# GalvoPrint.net
KiCad netlist of a schematic drawn in Altium Designer
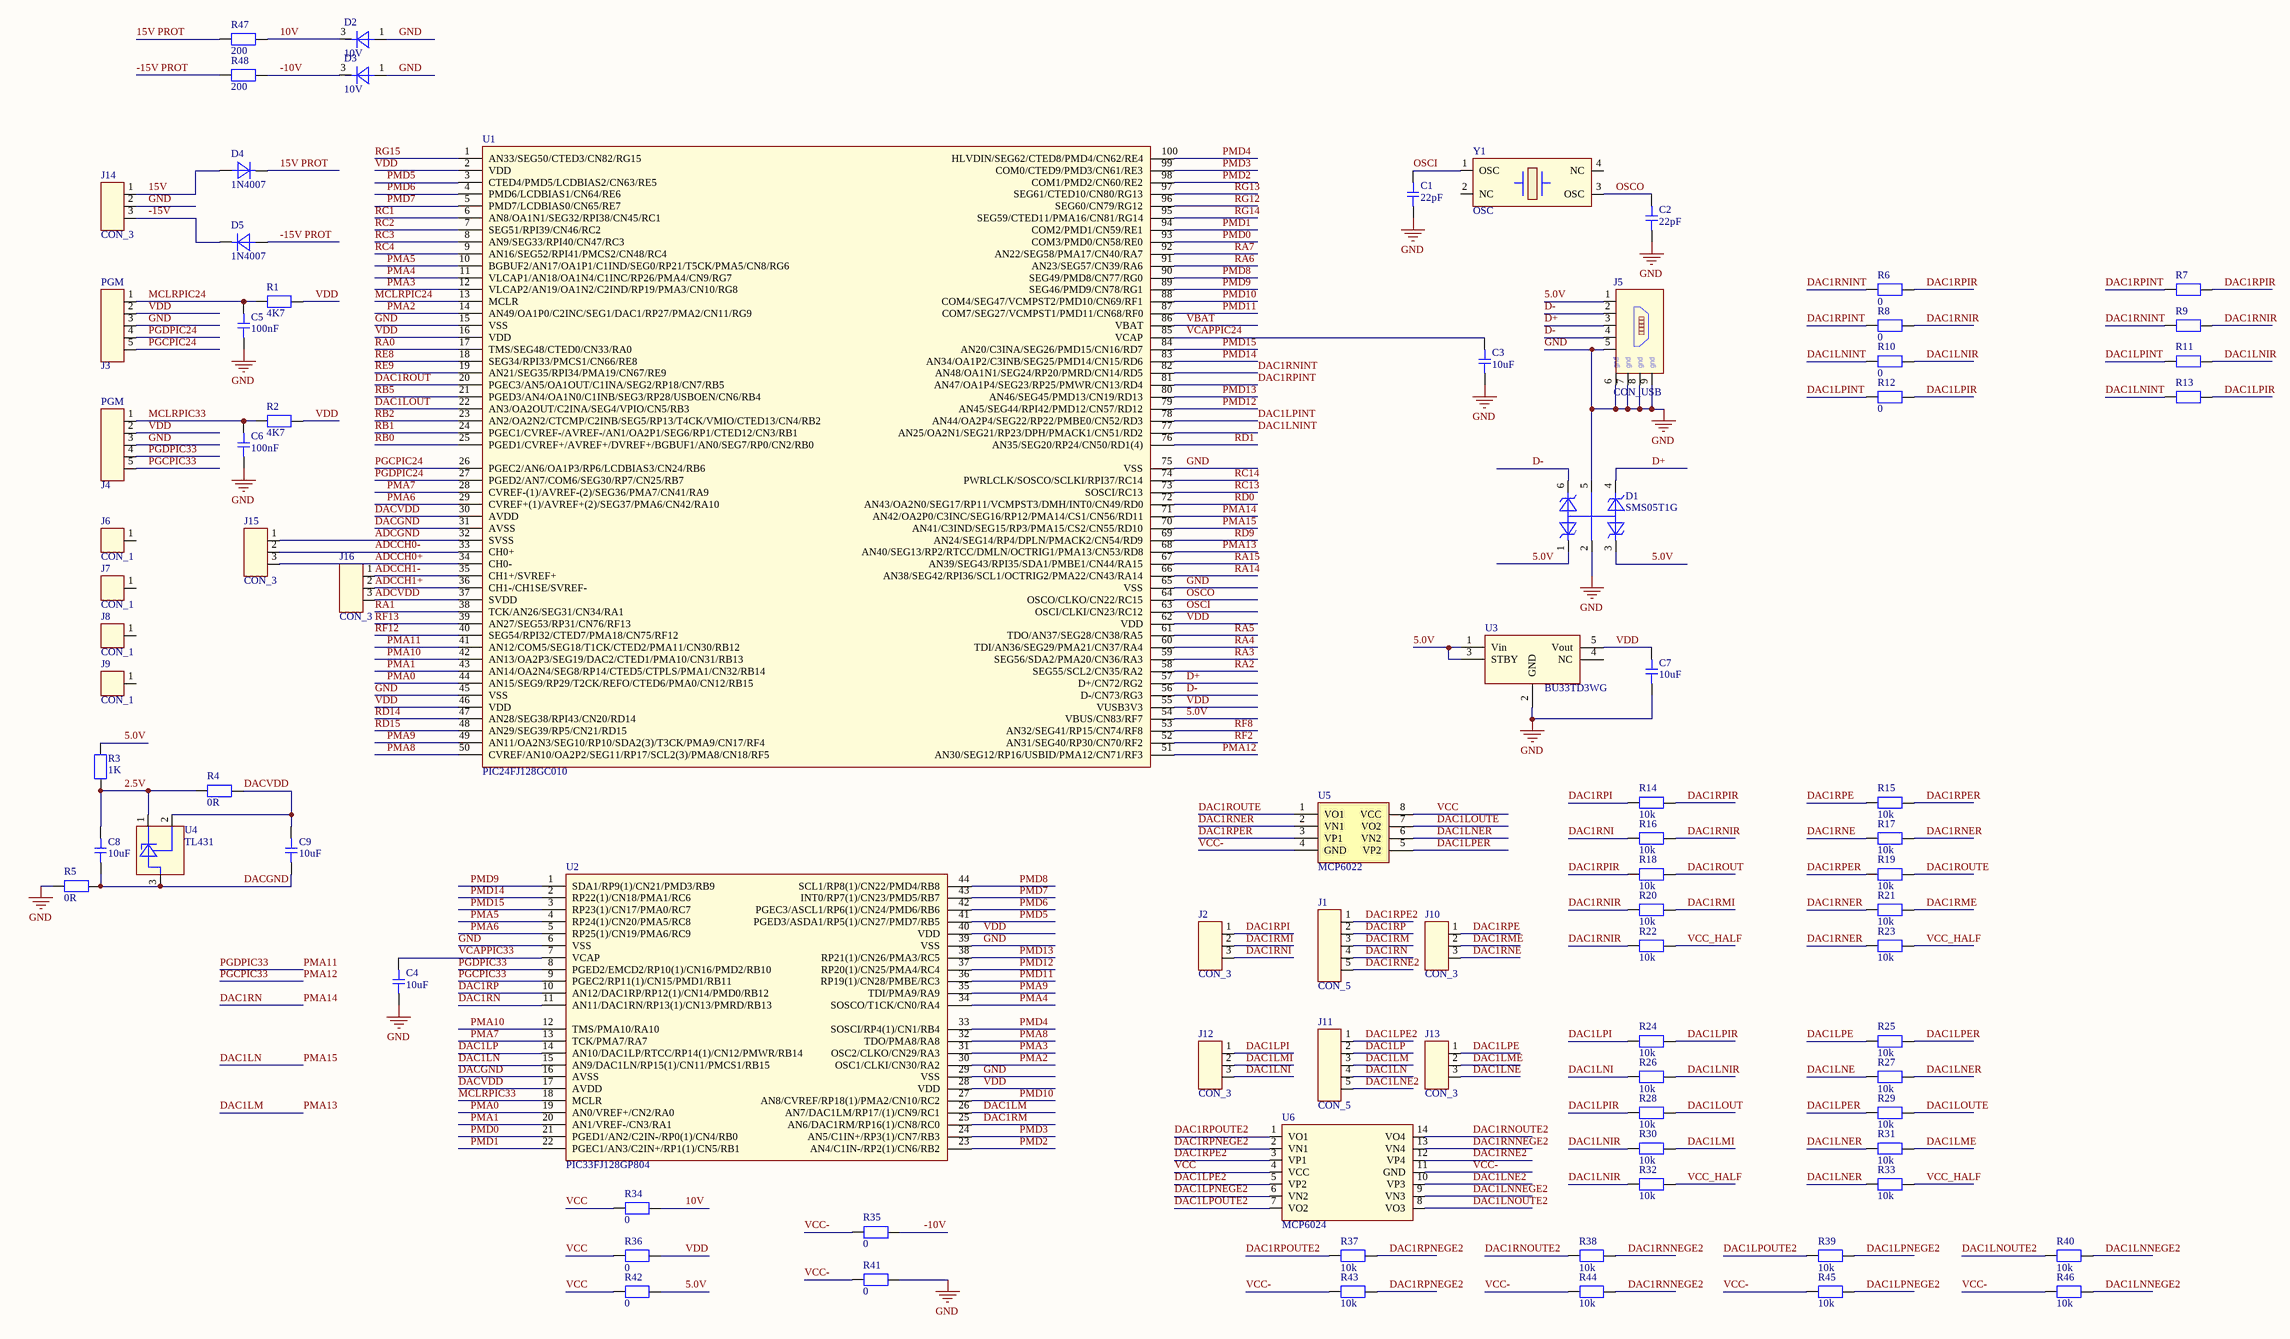
[diagram p0: GalvoPrint.SchDoc]

(export (version "E")
  (design (tool "Eeschema 10.0.6"))
  (components
    (comp (ref "C1")
      (value "22pF")
      (footprint "0603_C")
      (description "Capacitor")
      (fields (field (name "Comment") "C") (field (name "PUBLISHER") "Altium Limited"))
      (libsource (lib "HEX") (part "C"))
    )
    (comp (ref "C2")
      (value "22pF")
      (footprint "0603_C")
      (description "Capacitor")
      (fields (field (name "Comment") "C") (field (name "PUBLISHER") "Altium Limited"))
      (libsource (lib "HEX") (part "C"))
    )
    (comp (ref "C3")
      (value "10uF")
      (footprint "0603_C")
      (description "Capacitor")
      (fields (field (name "Comment") "C") (field (name "PUBLISHER") "Altium Limited"))
      (libsource (lib "HEX") (part "C"))
    )
    (comp (ref "C4")
      (value "10uF")
      (footprint "0603_C")
      (description "Capacitor")
      (fields (field (name "Comment") "C") (field (name "PUBLISHER") "Altium Limited"))
      (libsource (lib "HEX") (part "C"))
    )
    (comp (ref "C5")
      (value "100nF")
      (footprint "0603_C")
      (description "Capacitor")
      (fields (field (name "Comment") "C") (field (name "PUBLISHER") "Altium Limited"))
      (libsource (lib "HEX") (part "C"))
    )
    (comp (ref "C6")
      (value "100nF")
      (footprint "0603_C")
      (description "Capacitor")
      (fields (field (name "Comment") "C") (field (name "PUBLISHER") "Altium Limited"))
      (libsource (lib "HEX") (part "C"))
    )
    (comp (ref "C7")
      (value "10uF")
      (footprint "0603_C")
      (description "Capacitor")
      (fields (field (name "Comment") "C") (field (name "PUBLISHER") "Altium Limited"))
      (libsource (lib "HEX") (part "C"))
    )
    (comp (ref "C8")
      (value "10uF")
      (footprint "0603_C")
      (description "Capacitor")
      (fields (field (name "Comment") "C") (field (name "PUBLISHER") "Altium Limited"))
      (libsource (lib "HEX") (part "C"))
    )
    (comp (ref "C9")
      (value "10uF")
      (footprint "0603_C")
      (description "Capacitor")
      (fields (field (name "Comment") "C") (field (name "PUBLISHER") "Altium Limited"))
      (libsource (lib "HEX") (part "C"))
    )
    (comp (ref "D1")
      (value "SMS05T1G")
      (footprint "SOT23_6")
      (description "TVS like SMS05T1G")
      (libsource (lib "HEX") (part "D_TVS_QUAD_C1AA2AA5C3C4C6"))
    )
    (comp (ref "D2")
      (value "10V")
      (footprint "SOT23_3")
      (description "Diodes like 1N4148")
      (libsource (lib "HEX") (part "D_A1C3"))
    )
    (comp (ref "D3")
      (value "10V")
      (footprint "SOT23_3")
      (description "Diodes like 1N4148")
      (libsource (lib "HEX") (part "D_A1C3"))
    )
    (comp (ref "D4")
      (value "1N4007")
      (footprint "SMA")
      (description "Diode")
      (libsource (lib "HEX") (part "D"))
    )
    (comp (ref "D5")
      (value "1N4007")
      (footprint "SMA")
      (description "Diode")
      (libsource (lib "HEX") (part "D"))
    )
    (comp (ref "J1")
      (value "CON_5")
      (footprint "HDR_254_5")
      (description "Header 5 Pins")
      (libsource (lib "HEX") (part "CON_5"))
    )
    (comp (ref "J2")
      (value "CON_3")
      (footprint "HDR_254_3")
      (description "Header 3 Pins")
      (libsource (lib "HEX") (part "CON_3"))
    )
    (comp (ref "J3")
      (value "PGM")
      (footprint "HDR_254_5")
      (description "Header 5 Pins")
      (fields (field (name "Comment") "CON_5"))
      (libsource (lib "HEX") (part "CON_5"))
    )
    (comp (ref "J4")
      (value "PGM")
      (footprint "HDR_254_5")
      (description "Header 5 Pins")
      (fields (field (name "Comment") "CON_5"))
      (libsource (lib "HEX") (part "CON_5"))
    )
    (comp (ref "J5") (value "CON_USB") (footprint "CON_USB_MINI") (libsource (lib "HEX") (part "CON_USB")))
    (comp (ref "J6")
      (value "CON_1")
      (footprint "MOUNT_HOLE")
      (description "Mounting Hole")
      (libsource (lib "HEX") (part "CON_1"))
    )
    (comp (ref "J7")
      (value "CON_1")
      (footprint "MOUNT_HOLE")
      (description "Mounting Hole")
      (libsource (lib "HEX") (part "CON_1"))
    )
    (comp (ref "J8")
      (value "CON_1")
      (footprint "MOUNT_HOLE")
      (description "Mounting Hole")
      (libsource (lib "HEX") (part "CON_1"))
    )
    (comp (ref "J9")
      (value "CON_1")
      (footprint "MOUNT_HOLE")
      (description "Mounting Hole")
      (libsource (lib "HEX") (part "CON_1"))
    )
    (comp (ref "J10")
      (value "CON_3")
      (footprint "HDR_254_3")
      (description "Header 3 Pins")
      (libsource (lib "HEX") (part "CON_3"))
    )
    (comp (ref "J11")
      (value "CON_5")
      (footprint "HDR_254_5")
      (description "Header 5 Pins")
      (libsource (lib "HEX") (part "CON_5"))
    )
    (comp (ref "J12")
      (value "CON_3")
      (footprint "HDR_254_3")
      (description "Header 3 Pins")
      (libsource (lib "HEX") (part "CON_3"))
    )
    (comp (ref "J13")
      (value "CON_3")
      (footprint "HDR_254_3")
      (description "Header 3 Pins")
      (libsource (lib "HEX") (part "CON_3"))
    )
    (comp (ref "J14")
      (value "CON_3")
      (footprint "HDR_500_3")
      (description "Header 3 Pins")
      (libsource (lib "HEX") (part "CON_3"))
    )
    (comp (ref "J15")
      (value "CON_3")
      (footprint "HDR_254_3")
      (description "Header 3 Pins")
      (libsource (lib "HEX") (part "CON_3"))
    )
    (comp (ref "J16")
      (value "CON_3")
      (footprint "HDR_254_3")
      (description "Header 3 Pins")
      (libsource (lib "HEX") (part "CON_3"))
    )
    (comp (ref "R1")
      (value "4K7")
      (footprint "0603_R")
      (description "Resistor")
      (fields (field (name "Comment") "R") (field (name "PUBLISHER") "Altium Limited"))
      (libsource (lib "HEX") (part "R"))
    )
    (comp (ref "R2")
      (value "4K7")
      (footprint "0603_R")
      (description "Resistor")
      (fields (field (name "Comment") "R") (field (name "PUBLISHER") "Altium Limited"))
      (libsource (lib "HEX") (part "R"))
    )
    (comp (ref "R3")
      (value "1K")
      (footprint "0603_R")
      (description "Resistor")
      (fields (field (name "Comment") "R") (field (name "PUBLISHER") "Altium Limited"))
      (libsource (lib "HEX") (part "R"))
    )
    (comp (ref "R4")
      (value "0R")
      (footprint "0603_R")
      (description "Resistor")
      (fields (field (name "Comment") "R") (field (name "PUBLISHER") "Altium Limited"))
      (libsource (lib "HEX") (part "R"))
    )
    (comp (ref "R5")
      (value "0R")
      (footprint "0603_R")
      (description "Resistor")
      (fields (field (name "Comment") "R") (field (name "PUBLISHER") "Altium Limited"))
      (libsource (lib "HEX") (part "R"))
    )
    (comp (ref "R6")
      (value "0")
      (footprint "0603_R")
      (description "Resistor")
      (fields (field (name "PUBLISHER") "Altium Limited"))
      (libsource (lib "HEX") (part "R"))
    )
    (comp (ref "R7")
      (value "~")
      (footprint "0603_R")
      (description "Resistor")
      (fields (field (name "PUBLISHER") "Altium Limited"))
      (libsource (lib "HEX") (part "R"))
    )
    (comp (ref "R8")
      (value "0")
      (footprint "0603_R")
      (description "Resistor")
      (fields (field (name "PUBLISHER") "Altium Limited"))
      (libsource (lib "HEX") (part "R"))
    )
    (comp (ref "R9")
      (value "~")
      (footprint "0603_R")
      (description "Resistor")
      (fields (field (name "PUBLISHER") "Altium Limited"))
      (libsource (lib "HEX") (part "R"))
    )
    (comp (ref "R10")
      (value "0")
      (footprint "0603_R")
      (description "Resistor")
      (fields (field (name "PUBLISHER") "Altium Limited"))
      (libsource (lib "HEX") (part "R"))
    )
    (comp (ref "R11")
      (value "~")
      (footprint "0603_R")
      (description "Resistor")
      (fields (field (name "PUBLISHER") "Altium Limited"))
      (libsource (lib "HEX") (part "R"))
    )
    (comp (ref "R12")
      (value "0")
      (footprint "0603_R")
      (description "Resistor")
      (fields (field (name "PUBLISHER") "Altium Limited"))
      (libsource (lib "HEX") (part "R"))
    )
    (comp (ref "R13")
      (value "~")
      (footprint "0603_R")
      (description "Resistor")
      (fields (field (name "PUBLISHER") "Altium Limited"))
      (libsource (lib "HEX") (part "R"))
    )
    (comp (ref "R14")
      (value "10k")
      (footprint "0603_R")
      (description "Resistor")
      (fields (field (name "PUBLISHER") "Altium Limited"))
      (libsource (lib "HEX") (part "R"))
    )
    (comp (ref "R15")
      (value "10k")
      (footprint "0603_R")
      (description "Resistor")
      (fields (field (name "PUBLISHER") "Altium Limited"))
      (libsource (lib "HEX") (part "R"))
    )
    (comp (ref "R16")
      (value "10k")
      (footprint "0603_R")
      (description "Resistor")
      (fields (field (name "PUBLISHER") "Altium Limited"))
      (libsource (lib "HEX") (part "R"))
    )
    (comp (ref "R17")
      (value "10k")
      (footprint "0603_R")
      (description "Resistor")
      (fields (field (name "PUBLISHER") "Altium Limited"))
      (libsource (lib "HEX") (part "R"))
    )
    (comp (ref "R18")
      (value "10k")
      (footprint "0603_R")
      (description "Resistor")
      (fields (field (name "PUBLISHER") "Altium Limited"))
      (libsource (lib "HEX") (part "R"))
    )
    (comp (ref "R19")
      (value "10k")
      (footprint "0603_R")
      (description "Resistor")
      (fields (field (name "PUBLISHER") "Altium Limited"))
      (libsource (lib "HEX") (part "R"))
    )
    (comp (ref "R20")
      (value "10k")
      (footprint "0603_R")
      (description "Resistor")
      (fields (field (name "PUBLISHER") "Altium Limited"))
      (libsource (lib "HEX") (part "R"))
    )
    (comp (ref "R21")
      (value "10k")
      (footprint "0603_R")
      (description "Resistor")
      (fields (field (name "PUBLISHER") "Altium Limited"))
      (libsource (lib "HEX") (part "R"))
    )
    (comp (ref "R22")
      (value "10k")
      (footprint "0603_R")
      (description "Resistor")
      (fields (field (name "PUBLISHER") "Altium Limited"))
      (libsource (lib "HEX") (part "R"))
    )
    (comp (ref "R23")
      (value "10k")
      (footprint "0603_R")
      (description "Resistor")
      (fields (field (name "PUBLISHER") "Altium Limited"))
      (libsource (lib "HEX") (part "R"))
    )
    (comp (ref "R24")
      (value "10k")
      (footprint "0603_R")
      (description "Resistor")
      (fields (field (name "PUBLISHER") "Altium Limited"))
      (libsource (lib "HEX") (part "R"))
    )
    (comp (ref "R25")
      (value "10k")
      (footprint "0603_R")
      (description "Resistor")
      (fields (field (name "PUBLISHER") "Altium Limited"))
      (libsource (lib "HEX") (part "R"))
    )
    (comp (ref "R26")
      (value "10k")
      (footprint "0603_R")
      (description "Resistor")
      (fields (field (name "PUBLISHER") "Altium Limited"))
      (libsource (lib "HEX") (part "R"))
    )
    (comp (ref "R27")
      (value "10k")
      (footprint "0603_R")
      (description "Resistor")
      (fields (field (name "PUBLISHER") "Altium Limited"))
      (libsource (lib "HEX") (part "R"))
    )
    (comp (ref "R28")
      (value "10k")
      (footprint "0603_R")
      (description "Resistor")
      (fields (field (name "PUBLISHER") "Altium Limited"))
      (libsource (lib "HEX") (part "R"))
    )
    (comp (ref "R29")
      (value "10k")
      (footprint "0603_R")
      (description "Resistor")
      (fields (field (name "PUBLISHER") "Altium Limited"))
      (libsource (lib "HEX") (part "R"))
    )
    (comp (ref "R30")
      (value "10k")
      (footprint "0603_R")
      (description "Resistor")
      (fields (field (name "PUBLISHER") "Altium Limited"))
      (libsource (lib "HEX") (part "R"))
    )
    (comp (ref "R31")
      (value "10k")
      (footprint "0603_R")
      (description "Resistor")
      (fields (field (name "PUBLISHER") "Altium Limited"))
      (libsource (lib "HEX") (part "R"))
    )
    (comp (ref "R32")
      (value "10k")
      (footprint "0603_R")
      (description "Resistor")
      (fields (field (name "PUBLISHER") "Altium Limited"))
      (libsource (lib "HEX") (part "R"))
    )
    (comp (ref "R33")
      (value "10k")
      (footprint "0603_R")
      (description "Resistor")
      (fields (field (name "PUBLISHER") "Altium Limited"))
      (libsource (lib "HEX") (part "R"))
    )
    (comp (ref "R34")
      (value "0")
      (footprint "0603_R")
      (description "Resistor")
      (fields (field (name "PUBLISHER") "Altium Limited"))
      (libsource (lib "HEX") (part "R"))
    )
    (comp (ref "R35")
      (value "0")
      (footprint "0603_R")
      (description "Resistor")
      (fields (field (name "PUBLISHER") "Altium Limited"))
      (libsource (lib "HEX") (part "R"))
    )
    (comp (ref "R36")
      (value "0")
      (footprint "0603_R")
      (description "Resistor")
      (fields (field (name "PUBLISHER") "Altium Limited"))
      (libsource (lib "HEX") (part "R"))
    )
    (comp (ref "R37")
      (value "10k")
      (footprint "0603_R")
      (description "Resistor")
      (fields (field (name "PUBLISHER") "Altium Limited"))
      (libsource (lib "HEX") (part "R"))
    )
    (comp (ref "R38")
      (value "10k")
      (footprint "0603_R")
      (description "Resistor")
      (fields (field (name "PUBLISHER") "Altium Limited"))
      (libsource (lib "HEX") (part "R"))
    )
    (comp (ref "R39")
      (value "10k")
      (footprint "0603_R")
      (description "Resistor")
      (fields (field (name "PUBLISHER") "Altium Limited"))
      (libsource (lib "HEX") (part "R"))
    )
    (comp (ref "R40")
      (value "10k")
      (footprint "0603_R")
      (description "Resistor")
      (fields (field (name "PUBLISHER") "Altium Limited"))
      (libsource (lib "HEX") (part "R"))
    )
    (comp (ref "R41")
      (value "0")
      (footprint "0603_R")
      (description "Resistor")
      (fields (field (name "PUBLISHER") "Altium Limited"))
      (libsource (lib "HEX") (part "R"))
    )
    (comp (ref "R42")
      (value "0")
      (footprint "0603_R")
      (description "Resistor")
      (fields (field (name "PUBLISHER") "Altium Limited"))
      (libsource (lib "HEX") (part "R"))
    )
    (comp (ref "R43")
      (value "10k")
      (footprint "0603_R")
      (description "Resistor")
      (fields (field (name "PUBLISHER") "Altium Limited"))
      (libsource (lib "HEX") (part "R"))
    )
    (comp (ref "R44")
      (value "10k")
      (footprint "0603_R")
      (description "Resistor")
      (fields (field (name "PUBLISHER") "Altium Limited"))
      (libsource (lib "HEX") (part "R"))
    )
    (comp (ref "R45")
      (value "10k")
      (footprint "0603_R")
      (description "Resistor")
      (fields (field (name "PUBLISHER") "Altium Limited"))
      (libsource (lib "HEX") (part "R"))
    )
    (comp (ref "R46")
      (value "10k")
      (footprint "0603_R")
      (description "Resistor")
      (fields (field (name "PUBLISHER") "Altium Limited"))
      (libsource (lib "HEX") (part "R"))
    )
    (comp (ref "R47")
      (value "200")
      (footprint "0603_R")
      (description "Resistor")
      (fields (field (name "Comment") "R") (field (name "PUBLISHER") "Altium Limited"))
      (libsource (lib "HEX") (part "R"))
    )
    (comp (ref "R48")
      (value "200")
      (footprint "0603_R")
      (description "Resistor")
      (fields (field (name "Comment") "R") (field (name "PUBLISHER") "Altium Limited"))
      (libsource (lib "HEX") (part "R"))
    )
    (comp (ref "U1")
      (value "PIC24FJ128GC010")
      (footprint "TQFP_100")
      (fields (field (name "Comment") "IC_PIC24FJ128GC010"))
      (libsource (lib "HEX") (part "IC_PIC24FJ128GC010"))
    )
    (comp (ref "U2")
      (value "PIC33FJ128GP804")
      (footprint "TQFP_44")
      (fields (field (name "Comment") "IC_PIC33FJ128GP804"))
      (libsource (lib "HEX") (part "IC_PIC33FJ128GP804"))
    )
    (comp (ref "U3")
      (value "BU33TD3WG")
      (footprint "SOT23_5")
      (description "LDO 5 to 3.3V")
      (libsource (lib "HEX") (part "IC_BU33TD3WG"))
    )
    (comp (ref "U4")
      (value "TL431")
      (footprint "SOT23_3")
      (fields (field (name "Comment") "IC_TL431_SOT23_3"))
      (libsource (lib "HEX") (part "IC_TL431_SOT23_3"))
    )
    (comp (ref "U5")
      (value "MCP6022")
      (footprint "SOIC_8")
      (description "Opamp x 2")
      (libsource (lib "HEX") (part "IC_MCP6022"))
    )
    (comp (ref "U6")
      (value "MCP6024")
      (footprint "SOIC_14")
      (description "Opamp x 4")
      (libsource (lib "HEX") (part "IC_MCP6024"))
    )
    (comp (ref "Y1")
      (value "OSC")
      (footprint "OSC_DFN_2x2.5mm")
      (fields (field (name "Comment") "XTAL_OSC1OSC3"))
      (libsource (lib "HEX") (part "XTAL_OSC1OSC3"))
    )
  )
  (nets
    (net (code "1") (name "/-10V") (class "Default")
      (node (ref "D3") (pin "3") (pinfunction "C_3") (pintype "passive"))
      (node (ref "R35") (pin "2") (pinfunction "2_2") (pintype "passive"))
      (node (ref "R48") (pin "2") (pinfunction "2_2") (pintype "passive"))
    )
    (net (code "2") (name "/-15V") (class "Default")
      (node (ref "D5") (pin "1") (pinfunction "C_1") (pintype "passive"))
      (node (ref "J14") (pin "3") (pinfunction "3_3") (pintype "passive"))
    )
    (net (code "3") (name "/-15V PROT") (class "Default")
      (node (ref "D5") (pin "2") (pinfunction "A_2") (pintype "passive"))
      (node (ref "R48") (pin "1") (pinfunction "1_1") (pintype "passive"))
    )
    (net (code "4") (name "/2.5V") (class "Default")
      (node (ref "C8") (pin "2") (pinfunction "2_2") (pintype "passive"))
      (node (ref "R3") (pin "1") (pinfunction "1_1") (pintype "passive"))
      (node (ref "R4") (pin "1") (pinfunction "1_1") (pintype "passive"))
      (node (ref "U4") (pin "1") (pinfunction "Cathode_1") (pintype "passive"))
    )
    (net (code "5") (name "/5.0V") (class "Default")
      (node (ref "D1") (pin "1") (pinfunction "C1_1") (pintype "passive"))
      (node (ref "D1") (pin "3") (pinfunction "C2_3") (pintype "passive"))
      (node (ref "J5") (pin "1") (pinfunction "1_1") (pintype "passive"))
      (node (ref "R3") (pin "2") (pinfunction "2_2") (pintype "passive"))
      (node (ref "R42") (pin "2") (pinfunction "2_2") (pintype "passive"))
      (node (ref "U1") (pin "54") (pinfunction "VBUS/CN83/RF7_54") (pintype "passive"))
      (node (ref "U3") (pin "1") (pinfunction "Vin_1") (pintype "passive"))
      (node (ref "U3") (pin "3") (pinfunction "STBY_3") (pintype "passive"))
    )
    (net (code "6") (name "/10V") (class "Default")
      (node (ref "D2") (pin "3") (pinfunction "C_3") (pintype "passive"))
      (node (ref "R34") (pin "2") (pinfunction "2_2") (pintype "passive"))
      (node (ref "R47") (pin "2") (pinfunction "2_2") (pintype "passive"))
    )
    (net (code "7") (name "/15V") (class "Default")
      (node (ref "D4") (pin "2") (pinfunction "A_2") (pintype "passive"))
      (node (ref "J14") (pin "1") (pinfunction "1_1") (pintype "passive"))
    )
    (net (code "8") (name "/15V PROT") (class "Default")
      (node (ref "D4") (pin "1") (pinfunction "C_1") (pintype "passive"))
      (node (ref "R47") (pin "1") (pinfunction "1_1") (pintype "passive"))
    )
    (net (code "9") (name "/ADCCH0+") (class "Default")
      (node (ref "J15") (pin "3") (pinfunction "3_3") (pintype "passive"))
      (node (ref "U1") (pin "34") (pinfunction "CH0-_34") (pintype "passive"))
    )
    (net (code "10") (name "/ADCCH0-") (class "Default")
      (node (ref "J15") (pin "2") (pinfunction "2_2") (pintype "passive"))
      (node (ref "U1") (pin "33") (pinfunction "CH0+_33") (pintype "passive"))
    )
    (net (code "11") (name "/ADCCH1+") (class "Default")
      (node (ref "J16") (pin "2") (pinfunction "2_2") (pintype "passive"))
      (node (ref "U1") (pin "36") (pinfunction "CH1-/CH1SE/SVREF-_36") (pintype "passive"))
    )
    (net (code "12") (name "/ADCCH1-") (class "Default")
      (node (ref "J16") (pin "1") (pinfunction "1_1") (pintype "passive"))
      (node (ref "U1") (pin "35") (pinfunction "CH1+/SVREF+_35") (pintype "passive"))
    )
    (net (code "13") (name "/ADCGND") (class "Default")
      (node (ref "J15") (pin "1") (pinfunction "1_1") (pintype "passive"))
      (node (ref "U1") (pin "32") (pinfunction "SVSS_32") (pintype "passive"))
    )
    (net (code "14") (name "/ADCVDD") (class "Default")
      (node (ref "J16") (pin "3") (pinfunction "3_3") (pintype "passive"))
      (node (ref "U1") (pin "37") (pinfunction "SVDD_37") (pintype "passive"))
    )
    (net (code "15") (name "/D+") (class "Default")
      (node (ref "D1") (pin "4") (pinfunction "C3_4") (pintype "passive"))
      (node (ref "J5") (pin "3") (pinfunction "3_3") (pintype "passive"))
      (node (ref "U1") (pin "57") (pinfunction "D+/CN72/RG2_57") (pintype "passive"))
    )
    (net (code "16") (name "/D-") (class "Default")
      (node (ref "D1") (pin "6") (pinfunction "C4_6") (pintype "passive"))
      (node (ref "J5") (pin "2") (pinfunction "2_2") (pintype "passive"))
      (node (ref "J5") (pin "4") (pinfunction "4_4") (pintype "passive"))
      (node (ref "U1") (pin "56") (pinfunction "D-/CN73/RG3_56") (pintype "passive"))
    )
    (net (code "17") (name "/DAC1LM") (class "Default")
      (node (ref "J11") (pin "3") (pinfunction "3_3") (pintype "passive"))
      (node (ref "U1") (pin "68") (pinfunction "AN40/SEG13/RP2/RTCC/DMLN/OCTRIG1/PMA13/CN53/RD8_68") (pintype "passive"))
      (node (ref "U2") (pin "26") (pinfunction "AN7/DAC1LM/RP17/(1)/CN9/RC1_26") (pintype "passive"))
    )
    (net (code "18") (name "/DAC1LME") (class "Default")
      (node (ref "J13") (pin "2") (pinfunction "2_2") (pintype "passive"))
      (node (ref "R31") (pin "2") (pinfunction "2_2") (pintype "passive"))
    )
    (net (code "19") (name "/DAC1LMI") (class "Default")
      (node (ref "J12") (pin "2") (pinfunction "2_2") (pintype "passive"))
      (node (ref "R30") (pin "2") (pinfunction "2_2") (pintype "passive"))
    )
    (net (code "20") (name "/DAC1LN") (class "Default")
      (node (ref "J11") (pin "4") (pinfunction "4_4") (pintype "passive"))
      (node (ref "U1") (pin "70") (pinfunction "AN41/C3IND/SEG15/RP3/PMA15/CS2/CN55/RD10_70") (pintype "passive"))
      (node (ref "U2") (pin "15") (pinfunction "AN9/DAC1LN/RP15(1)/CN11/PMCS1/RB15_15") (pintype "passive"))
    )
    (net (code "21") (name "/DAC1LNE") (class "Default")
      (node (ref "J13") (pin "3") (pinfunction "3_3") (pintype "passive"))
      (node (ref "R27") (pin "1") (pinfunction "1_1") (pintype "passive"))
    )
    (net (code "22") (name "/DAC1LNE2") (class "Default")
      (node (ref "J11") (pin "5") (pinfunction "5_5") (pintype "passive"))
      (node (ref "U6") (pin "10") (pinfunction "VP3_10") (pintype "passive"))
    )
    (net (code "23") (name "/DAC1LNER") (class "Default")
      (node (ref "R27") (pin "2") (pinfunction "2_2") (pintype "passive"))
      (node (ref "R31") (pin "1") (pinfunction "1_1") (pintype "passive"))
      (node (ref "R33") (pin "1") (pinfunction "1_1") (pintype "passive"))
      (node (ref "U5") (pin "6") (pinfunction "VN2_6") (pintype "passive"))
    )
    (net (code "24") (name "/DAC1LNI") (class "Default")
      (node (ref "J12") (pin "3") (pinfunction "3_3") (pintype "passive"))
      (node (ref "R26") (pin "1") (pinfunction "1_1") (pintype "passive"))
    )
    (net (code "25") (name "/DAC1LNINT") (class "Default")
      (node (ref "R10") (pin "1") (pinfunction "1_1") (pintype "passive"))
      (node (ref "R13") (pin "1") (pinfunction "1_1") (pintype "passive"))
      (node (ref "U1") (pin "77") (pinfunction "AN25/OA2N1/SEG21/RP23/DPH/PMACK1/CN51/RD2_77") (pintype "passive"))
    )
    (net (code "26") (name "/DAC1LNIR") (class "Default")
      (node (ref "R10") (pin "2") (pinfunction "2_2") (pintype "passive"))
      (node (ref "R11") (pin "2") (pinfunction "2_2") (pintype "passive"))
      (node (ref "R26") (pin "2") (pinfunction "2_2") (pintype "passive"))
      (node (ref "R30") (pin "1") (pinfunction "1_1") (pintype "passive"))
      (node (ref "R32") (pin "1") (pinfunction "1_1") (pintype "passive"))
    )
    (net (code "27") (name "/DAC1LNNEGE2") (class "Default")
      (node (ref "R40") (pin "2") (pinfunction "2_2") (pintype "passive"))
      (node (ref "R46") (pin "2") (pinfunction "2_2") (pintype "passive"))
      (node (ref "U6") (pin "9") (pinfunction "VN3_9") (pintype "passive"))
    )
    (net (code "28") (name "/DAC1LNOUTE2") (class "Default")
      (node (ref "R40") (pin "1") (pinfunction "1_1") (pintype "passive"))
      (node (ref "U6") (pin "8") (pinfunction "VO3_8") (pintype "passive"))
    )
    (net (code "29") (name "/DAC1LOUT") (class "Default")
      (node (ref "R28") (pin "2") (pinfunction "2_2") (pintype "passive"))
      (node (ref "U1") (pin "22") (pinfunction "AN3/OA2OUT/C2INA/SEG4/VPIO/CN5/RB3_22") (pintype "passive"))
    )
    (net (code "30") (name "/DAC1LOUTE") (class "Default")
      (node (ref "R29") (pin "2") (pinfunction "2_2") (pintype "passive"))
      (node (ref "U5") (pin "7") (pinfunction "VO2_7") (pintype "passive"))
    )
    (net (code "31") (name "/DAC1LP") (class "Default")
      (node (ref "J11") (pin "2") (pinfunction "2_2") (pintype "passive"))
      (node (ref "U2") (pin "14") (pinfunction "AN10/DAC1LP/RTCC/RP14(1)/CN12/PMWR/RB14_14") (pintype "passive"))
    )
    (net (code "32") (name "/DAC1LPE") (class "Default")
      (node (ref "J13") (pin "1") (pinfunction "1_1") (pintype "passive"))
      (node (ref "R25") (pin "1") (pinfunction "1_1") (pintype "passive"))
    )
    (net (code "33") (name "/DAC1LPE2") (class "Default")
      (node (ref "J11") (pin "1") (pinfunction "1_1") (pintype "passive"))
      (node (ref "U6") (pin "5") (pinfunction "VP2_5") (pintype "passive"))
    )
    (net (code "34") (name "/DAC1LPER") (class "Default")
      (node (ref "R25") (pin "2") (pinfunction "2_2") (pintype "passive"))
      (node (ref "R29") (pin "1") (pinfunction "1_1") (pintype "passive"))
      (node (ref "U5") (pin "5") (pinfunction "VP2_5") (pintype "passive"))
    )
    (net (code "35") (name "/DAC1LPI") (class "Default")
      (node (ref "J12") (pin "1") (pinfunction "1_1") (pintype "passive"))
      (node (ref "R24") (pin "1") (pinfunction "1_1") (pintype "passive"))
    )
    (net (code "36") (name "/DAC1LPINT") (class "Default")
      (node (ref "R11") (pin "1") (pinfunction "1_1") (pintype "passive"))
      (node (ref "R12") (pin "1") (pinfunction "1_1") (pintype "passive"))
      (node (ref "U1") (pin "78") (pinfunction "AN44/OA2P4/SEG22/RP22/PMBE0/CN52/RD3_78") (pintype "passive"))
    )
    (net (code "37") (name "/DAC1LPIR") (class "Default")
      (node (ref "R12") (pin "2") (pinfunction "2_2") (pintype "passive"))
      (node (ref "R13") (pin "2") (pinfunction "2_2") (pintype "passive"))
      (node (ref "R24") (pin "2") (pinfunction "2_2") (pintype "passive"))
      (node (ref "R28") (pin "1") (pinfunction "1_1") (pintype "passive"))
    )
    (net (code "38") (name "/DAC1LPNEGE2") (class "Default")
      (node (ref "R39") (pin "2") (pinfunction "2_2") (pintype "passive"))
      (node (ref "R45") (pin "2") (pinfunction "2_2") (pintype "passive"))
      (node (ref "U6") (pin "6") (pinfunction "VN2_6") (pintype "passive"))
    )
    (net (code "39") (name "/DAC1LPOUTE2") (class "Default")
      (node (ref "R39") (pin "1") (pinfunction "1_1") (pintype "passive"))
      (node (ref "U6") (pin "7") (pinfunction "VO2_7") (pintype "passive"))
    )
    (net (code "40") (name "/DAC1RM") (class "Default")
      (node (ref "J1") (pin "3") (pinfunction "3_3") (pintype "passive"))
      (node (ref "U2") (pin "25") (pinfunction "AN6/DAC1RM/RP16(1)/CN8/RC0_25") (pintype "passive"))
    )
    (net (code "41") (name "/DAC1RME") (class "Default")
      (node (ref "J10") (pin "2") (pinfunction "2_2") (pintype "passive"))
      (node (ref "R21") (pin "2") (pinfunction "2_2") (pintype "passive"))
    )
    (net (code "42") (name "/DAC1RMI") (class "Default")
      (node (ref "J2") (pin "2") (pinfunction "2_2") (pintype "passive"))
      (node (ref "R20") (pin "2") (pinfunction "2_2") (pintype "passive"))
    )
    (net (code "43") (name "/DAC1RN") (class "Default")
      (node (ref "J1") (pin "4") (pinfunction "4_4") (pintype "passive"))
      (node (ref "U1") (pin "71") (pinfunction "AN42/OA2P0/C3INC/SEG16/RP12/PMA14/CS1/CN56/RD11_71") (pintype "passive"))
      (node (ref "U2") (pin "11") (pinfunction "AN11/DAC1RN/RP13(1)/CN13/PMRD/RB13_11") (pintype "passive"))
    )
    (net (code "44") (name "/DAC1RNE") (class "Default")
      (node (ref "J10") (pin "3") (pinfunction "3_3") (pintype "passive"))
      (node (ref "R17") (pin "1") (pinfunction "1_1") (pintype "passive"))
    )
    (net (code "45") (name "/DAC1RNE2") (class "Default")
      (node (ref "J1") (pin "5") (pinfunction "5_5") (pintype "passive"))
      (node (ref "U6") (pin "12") (pinfunction "VP4_12") (pintype "passive"))
    )
    (net (code "46") (name "/DAC1RNER") (class "Default")
      (node (ref "R17") (pin "2") (pinfunction "2_2") (pintype "passive"))
      (node (ref "R21") (pin "1") (pinfunction "1_1") (pintype "passive"))
      (node (ref "R23") (pin "1") (pinfunction "1_1") (pintype "passive"))
      (node (ref "U5") (pin "2") (pinfunction "VN1_2") (pintype "passive"))
    )
    (net (code "47") (name "/DAC1RNI") (class "Default")
      (node (ref "J2") (pin "3") (pinfunction "3_3") (pintype "passive"))
      (node (ref "R16") (pin "1") (pinfunction "1_1") (pintype "passive"))
    )
    (net (code "48") (name "/DAC1RNINT") (class "Default")
      (node (ref "R6") (pin "1") (pinfunction "1_1") (pintype "passive"))
      (node (ref "R9") (pin "1") (pinfunction "1_1") (pintype "passive"))
      (node (ref "U1") (pin "82") (pinfunction "AN48/OA1N1/SEG24/RP20/PMRD/CN14/RD5_82") (pintype "passive"))
    )
    (net (code "49") (name "/DAC1RNIR") (class "Default")
      (node (ref "R16") (pin "2") (pinfunction "2_2") (pintype "passive"))
      (node (ref "R20") (pin "1") (pinfunction "1_1") (pintype "passive"))
      (node (ref "R22") (pin "1") (pinfunction "1_1") (pintype "passive"))
      (node (ref "R8") (pin "2") (pinfunction "2_2") (pintype "passive"))
      (node (ref "R9") (pin "2") (pinfunction "2_2") (pintype "passive"))
    )
    (net (code "50") (name "/DAC1RNNEGE2") (class "Default")
      (node (ref "R38") (pin "2") (pinfunction "2_2") (pintype "passive"))
      (node (ref "R44") (pin "2") (pinfunction "2_2") (pintype "passive"))
      (node (ref "U6") (pin "13") (pinfunction "VN4_13") (pintype "passive"))
    )
    (net (code "51") (name "/DAC1RNOUTE2") (class "Default")
      (node (ref "R38") (pin "1") (pinfunction "1_1") (pintype "passive"))
      (node (ref "U6") (pin "14") (pinfunction "VO4_14") (pintype "passive"))
    )
    (net (code "52") (name "/DAC1ROUT") (class "Default")
      (node (ref "R18") (pin "2") (pinfunction "2_2") (pintype "passive"))
      (node (ref "U1") (pin "20") (pinfunction "PGEC3/AN5/OA1OUT/C1INA/SEG2/RP18/CN7/RB5_20") (pintype "passive"))
    )
    (net (code "53") (name "/DAC1ROUTE") (class "Default")
      (node (ref "R19") (pin "2") (pinfunction "2_2") (pintype "passive"))
      (node (ref "U5") (pin "1") (pinfunction "VO1_1") (pintype "passive"))
    )
    (net (code "54") (name "/DAC1RP") (class "Default")
      (node (ref "J1") (pin "2") (pinfunction "2_2") (pintype "passive"))
      (node (ref "U2") (pin "10") (pinfunction "AN12/DAC1RP/RP12(1)/CN14/PMD0/RB12_10") (pintype "passive"))
    )
    (net (code "55") (name "/DAC1RPE") (class "Default")
      (node (ref "J10") (pin "1") (pinfunction "1_1") (pintype "passive"))
      (node (ref "R15") (pin "1") (pinfunction "1_1") (pintype "passive"))
    )
    (net (code "56") (name "/DAC1RPE2") (class "Default")
      (node (ref "J1") (pin "1") (pinfunction "1_1") (pintype "passive"))
      (node (ref "U6") (pin "3") (pinfunction "VP1_3") (pintype "passive"))
    )
    (net (code "57") (name "/DAC1RPER") (class "Default")
      (node (ref "R15") (pin "2") (pinfunction "2_2") (pintype "passive"))
      (node (ref "R19") (pin "1") (pinfunction "1_1") (pintype "passive"))
      (node (ref "U5") (pin "3") (pinfunction "VP1_3") (pintype "passive"))
    )
    (net (code "58") (name "/DAC1RPI") (class "Default")
      (node (ref "J2") (pin "1") (pinfunction "1_1") (pintype "passive"))
      (node (ref "R14") (pin "1") (pinfunction "1_1") (pintype "passive"))
    )
    (net (code "59") (name "/DAC1RPINT") (class "Default")
      (node (ref "R7") (pin "1") (pinfunction "1_1") (pintype "passive"))
      (node (ref "R8") (pin "1") (pinfunction "1_1") (pintype "passive"))
      (node (ref "U1") (pin "81") (pinfunction "AN47/OA1P4/SEG23/RP25/PMWR/CN13/RD4_81") (pintype "passive"))
    )
    (net (code "60") (name "/DAC1RPIR") (class "Default")
      (node (ref "R14") (pin "2") (pinfunction "2_2") (pintype "passive"))
      (node (ref "R18") (pin "1") (pinfunction "1_1") (pintype "passive"))
      (node (ref "R6") (pin "2") (pinfunction "2_2") (pintype "passive"))
      (node (ref "R7") (pin "2") (pinfunction "2_2") (pintype "passive"))
    )
    (net (code "61") (name "/DAC1RPNEGE2") (class "Default")
      (node (ref "R37") (pin "2") (pinfunction "2_2") (pintype "passive"))
      (node (ref "R43") (pin "2") (pinfunction "2_2") (pintype "passive"))
      (node (ref "U6") (pin "2") (pinfunction "VN1_2") (pintype "passive"))
    )
    (net (code "62") (name "/DAC1RPOUTE2") (class "Default")
      (node (ref "R37") (pin "1") (pinfunction "1_1") (pintype "passive"))
      (node (ref "U6") (pin "1") (pinfunction "VO1_1") (pintype "passive"))
    )
    (net (code "63") (name "/DACGND") (class "Default")
      (node (ref "C8") (pin "1") (pinfunction "1_1") (pintype "passive"))
      (node (ref "C9") (pin "1") (pinfunction "1_1") (pintype "passive"))
      (node (ref "R5") (pin "2") (pinfunction "2_2") (pintype "passive"))
      (node (ref "U1") (pin "31") (pinfunction "AVSS_31") (pintype "passive"))
      (node (ref "U2") (pin "16") (pinfunction "AVSS_16") (pintype "passive"))
      (node (ref "U4") (pin "3") (pinfunction "Anode_3") (pintype "passive"))
    )
    (net (code "64") (name "/DACVDD") (class "Default")
      (node (ref "C9") (pin "2") (pinfunction "2_2") (pintype "passive"))
      (node (ref "R4") (pin "2") (pinfunction "2_2") (pintype "passive"))
      (node (ref "U1") (pin "30") (pinfunction "AVDD_30") (pintype "passive"))
      (node (ref "U2") (pin "17") (pinfunction "AVDD_17") (pintype "passive"))
      (node (ref "U4") (pin "2") (pinfunction "Ref_2") (pintype "passive"))
    )
    (net (code "65") (name "/MCLRPIC24") (class "Default")
      (node (ref "C5") (pin "2") (pinfunction "2_2") (pintype "passive"))
      (node (ref "J3") (pin "1") (pinfunction "1_1") (pintype "passive"))
      (node (ref "R1") (pin "1") (pinfunction "1_1") (pintype "passive"))
      (node (ref "U1") (pin "13") (pinfunction "MCLR_13") (pintype "passive"))
    )
    (net (code "66") (name "/MCLRPIC33") (class "Default")
      (node (ref "C6") (pin "2") (pinfunction "2_2") (pintype "passive"))
      (node (ref "J4") (pin "1") (pinfunction "1_1") (pintype "passive"))
      (node (ref "R2") (pin "1") (pinfunction "1_1") (pintype "passive"))
      (node (ref "U2") (pin "18") (pinfunction "MCLR_18") (pintype "passive"))
    )
    (net (code "67") (name "/OSCI") (class "Default")
      (node (ref "C1") (pin "2") (pinfunction "2_2") (pintype "passive"))
      (node (ref "U1") (pin "63") (pinfunction "OSCI/CLKI/CN23/RC12_63") (pintype "passive"))
      (node (ref "Y1") (pin "1") (pinfunction "OSC_1") (pintype "passive"))
    )
    (net (code "68") (name "/OSCO") (class "Default")
      (node (ref "C2") (pin "2") (pinfunction "2_2") (pintype "passive"))
      (node (ref "U1") (pin "64") (pinfunction "OSCO/CLKO/CN22/RC15_64") (pintype "passive"))
      (node (ref "Y1") (pin "3") (pinfunction "OSC_3") (pintype "passive"))
    )
    (net (code "69") (name "/PGCPIC24") (class "Default")
      (node (ref "J3") (pin "5") (pinfunction "5_5") (pintype "passive"))
      (node (ref "U1") (pin "26") (pinfunction "PGEC2/AN6/OA1P3/RP6/LCDBIAS3/CN24/RB6_26") (pintype "passive"))
    )
    (net (code "70") (name "/PGCPIC33") (class "Default")
      (node (ref "J4") (pin "5") (pinfunction "5_5") (pintype "passive"))
      (node (ref "U1") (pin "51") (pinfunction "AN30/SEG12/RP16/USBID/PMA12/CN71/RF3_51") (pintype "passive"))
      (node (ref "U2") (pin "9") (pinfunction "PGEC2/RP11(1)/CN15/PMD1/RB11_9") (pintype "passive"))
    )
    (net (code "71") (name "/PGDPIC24") (class "Default")
      (node (ref "J3") (pin "4") (pinfunction "4_4") (pintype "passive"))
      (node (ref "U1") (pin "27") (pinfunction "PGED2/AN7/COM6/SEG30/RP7/CN25/RB7_27") (pintype "passive"))
    )
    (net (code "72") (name "/PGDPIC33") (class "Default")
      (node (ref "J4") (pin "4") (pinfunction "4_4") (pintype "passive"))
      (node (ref "U1") (pin "41") (pinfunction "AN12/COM5/SEG18/T1CK/CTED2/PMA11/CN30/RB12_41") (pintype "passive"))
      (node (ref "U2") (pin "8") (pinfunction "PGED2/EMCD2/RP10(1)/CN16/PMD2/RB10_8") (pintype "passive"))
    )
    (net (code "73") (name "/PMA0") (class "Default")
      (node (ref "U1") (pin "44") (pinfunction "AN15/SEG9/RP29/T2CK/REFO/CTED6/PMA0/CN12/RB15_44") (pintype "passive"))
      (node (ref "U2") (pin "19") (pinfunction "AN0/VREF+/CN2/RA0_19") (pintype "passive"))
    )
    (net (code "74") (name "/PMA1") (class "Default")
      (node (ref "U1") (pin "43") (pinfunction "AN14/OA2N4/SEG8/RP14/CTED5/CTPLS/PMA1/CN32/RB14_43") (pintype "passive"))
      (node (ref "U2") (pin "20") (pinfunction "AN1/VREF-/CN3/RA1_20") (pintype "passive"))
    )
    (net (code "75") (name "/PMA2") (class "Default")
      (node (ref "U1") (pin "14") (pinfunction "AN49/OA1P0/C2INC/SEG1/DAC1/RP27/PMA2/CN11/RG9_14") (pintype "passive"))
      (node (ref "U2") (pin "30") (pinfunction "OSC1/CLKI/CN30/RA2_30") (pintype "passive"))
    )
    (net (code "76") (name "/PMA3") (class "Default")
      (node (ref "U1") (pin "12") (pinfunction "VLCAP2/AN19/OA1N2/C2IND/RP19/PMA3/CN10/RG8_12") (pintype "passive"))
      (node (ref "U2") (pin "31") (pinfunction "OSC2/CLKO/CN29/RA3_31") (pintype "passive"))
    )
    (net (code "77") (name "/PMA4") (class "Default")
      (node (ref "U1") (pin "11") (pinfunction "VLCAP1/AN18/OA1N4/C1INC/RP26/PMA4/CN9/RG7_11") (pintype "passive"))
      (node (ref "U2") (pin "34") (pinfunction "SOSCO/T1CK/CN0/RA4_34") (pintype "passive"))
    )
    (net (code "78") (name "/PMA5") (class "Default")
      (node (ref "U1") (pin "10") (pinfunction "BGBUF2/AN17/OA1P1/C1IND/SEG0/RP21/T5CK/PMA5/CN8/RG6_10") (pintype "passive"))
      (node (ref "U2") (pin "4") (pinfunction "RP24(1)/CN20/PMA5/RC8_4") (pintype "passive"))
    )
    (net (code "79") (name "/PMA6") (class "Default")
      (node (ref "U1") (pin "29") (pinfunction "CVREF+(1)/AVREF+(2)/SEG37/PMA6/CN42/RA10_29") (pintype "passive"))
      (node (ref "U2") (pin "5") (pinfunction "RP25(1)/CN19/PMA6/RC9_5") (pintype "passive"))
    )
    (net (code "80") (name "/PMA7") (class "Default")
      (node (ref "U1") (pin "28") (pinfunction "CVREF-(1)/AVREF-(2)/SEG36/PMA7/CN41/RA9_28") (pintype "passive"))
      (node (ref "U2") (pin "13") (pinfunction "TCK/PMA7/RA7_13") (pintype "passive"))
    )
    (net (code "81") (name "/PMA8") (class "Default")
      (node (ref "U1") (pin "50") (pinfunction "CVREF/AN10/OA2P2/SEG11/RP17/SCL2(3)/PMA8/CN18/RF5_50") (pintype "passive"))
      (node (ref "U2") (pin "32") (pinfunction "TDO/PMA8/RA8_32") (pintype "passive"))
    )
    (net (code "82") (name "/PMA9") (class "Default")
      (node (ref "U1") (pin "49") (pinfunction "AN11/OA2N3/SEG10/RP10/SDA2(3)/T3CK/PMA9/CN17/RF4_49") (pintype "passive"))
      (node (ref "U2") (pin "35") (pinfunction "TDI/PMA9/RA9_35") (pintype "passive"))
    )
    (net (code "83") (name "/PMA10") (class "Default")
      (node (ref "U1") (pin "42") (pinfunction "AN13/OA2P3/SEG19/DAC2/CTED1/PMA10/CN31/RB13_42") (pintype "passive"))
      (node (ref "U2") (pin "12") (pinfunction "TMS/PMA10/RA10_12") (pintype "passive"))
    )
    (net (code "84") (name "/PMD0") (class "Default")
      (node (ref "U1") (pin "93") (pinfunction "COM3/PMD0/CN58/RE0_93") (pintype "passive"))
      (node (ref "U2") (pin "21") (pinfunction "PGED1/AN2/C2IN-/RP0(1)/CN4/RB0_21") (pintype "passive"))
    )
    (net (code "85") (name "/PMD1") (class "Default")
      (node (ref "U1") (pin "94") (pinfunction "COM2/PMD1/CN59/RE1_94") (pintype "passive"))
      (node (ref "U2") (pin "22") (pinfunction "PGEC1/AN3/C2IN+/RP1(1)/CN5/RB1_22") (pintype "passive"))
    )
    (net (code "86") (name "/PMD2") (class "Default")
      (node (ref "U1") (pin "98") (pinfunction "COM1/PMD2/CN60/RE2_98") (pintype "passive"))
      (node (ref "U2") (pin "23") (pinfunction "AN4/C1IN-/RP2(1)/CN6/RB2_23") (pintype "passive"))
    )
    (net (code "87") (name "/PMD3") (class "Default")
      (node (ref "U1") (pin "99") (pinfunction "COM0/CTED9/PMD3/CN61/RE3_99") (pintype "passive"))
      (node (ref "U2") (pin "24") (pinfunction "AN5/C1IN+/RP3(1)/CN7/RB3_24") (pintype "passive"))
    )
    (net (code "88") (name "/PMD4") (class "Default")
      (node (ref "U1") (pin "100") (pinfunction "HLVDIN/SEG62/CTED8/PMD4/CN62/RE4_100") (pintype "passive"))
      (node (ref "U2") (pin "33") (pinfunction "SOSCI/RP4(1)/CN1/RB4_33") (pintype "passive"))
    )
    (net (code "89") (name "/PMD5") (class "Default")
      (node (ref "U1") (pin "3") (pinfunction "CTED4/PMD5/LCDBIAS2/CN63/RE5_3") (pintype "passive"))
      (node (ref "U2") (pin "41") (pinfunction "PGED3/ASDA1/RP5(1)/CN27/PMD7/RB5_41") (pintype "passive"))
    )
    (net (code "90") (name "/PMD6") (class "Default")
      (node (ref "U1") (pin "4") (pinfunction "PMD6/LCDBIAS1/CN64/RE6_4") (pintype "passive"))
      (node (ref "U2") (pin "42") (pinfunction "PGEC3/ASCL1/RP6(1)/CN24/PMD6/RB6_42") (pintype "passive"))
    )
    (net (code "91") (name "/PMD7") (class "Default")
      (node (ref "U1") (pin "5") (pinfunction "PMD7/LCDBIAS0/CN65/RE7_5") (pintype "passive"))
      (node (ref "U2") (pin "43") (pinfunction "INT0/RP7(1)/CN23/PMD5/RB7_43") (pintype "passive"))
    )
    (net (code "92") (name "/PMD8") (class "Default")
      (node (ref "U1") (pin "90") (pinfunction "SEG49/PMD8/CN77/RG0_90") (pintype "passive"))
      (node (ref "U2") (pin "44") (pinfunction "SCL1/RP8(1)/CN22/PMD4/RB8_44") (pintype "passive"))
    )
    (net (code "93") (name "/PMD9") (class "Default")
      (node (ref "U1") (pin "89") (pinfunction "SEG46/PMD9/CN78/RG1_89") (pintype "passive"))
      (node (ref "U2") (pin "1") (pinfunction "SDA1/RP9(1)/CN21/PMD3/RB9_1") (pintype "passive"))
    )
    (net (code "94") (name "/PMD10") (class "Default")
      (node (ref "U1") (pin "88") (pinfunction "COM4/SEG47/VCMPST2/PMD10/CN69/RF1_88") (pintype "passive"))
      (node (ref "U2") (pin "27") (pinfunction "AN8/CVREF/RP18(1)/PMA2/CN10/RC2_27") (pintype "passive"))
    )
    (net (code "95") (name "/PMD11") (class "Default")
      (node (ref "U1") (pin "87") (pinfunction "COM7/SEG27/VCMPST1/PMD11/CN68/RF0_87") (pintype "passive"))
      (node (ref "U2") (pin "36") (pinfunction "RP19(1)/CN28/PMBE/RC3_36") (pintype "passive"))
    )
    (net (code "96") (name "/PMD12") (class "Default")
      (node (ref "U1") (pin "79") (pinfunction "AN45/SEG44/RPI42/PMD12/CN57/RD12_79") (pintype "passive"))
      (node (ref "U2") (pin "37") (pinfunction "RP20(1)/CN25/PMA4/RC4_37") (pintype "passive"))
    )
    (net (code "97") (name "/PMD13") (class "Default")
      (node (ref "U1") (pin "80") (pinfunction "AN46/SEG45/PMD13/CN19/RD13_80") (pintype "passive"))
      (node (ref "U2") (pin "38") (pinfunction "RP21(1)/CN26/PMA3/RC5_38") (pintype "passive"))
    )
    (net (code "98") (name "/PMD14") (class "Default")
      (node (ref "U1") (pin "83") (pinfunction "AN34/OA1P2/C3INB/SEG25/PMD14/CN15/RD6_83") (pintype "passive"))
      (node (ref "U2") (pin "2") (pinfunction "RP22(1)/CN18/PMA1/RC6_2") (pintype "passive"))
    )
    (net (code "99") (name "/PMD15") (class "Default")
      (node (ref "U1") (pin "84") (pinfunction "AN20/C3INA/SEG26/PMD15/CN16/RD7_84") (pintype "passive"))
      (node (ref "U2") (pin "3") (pinfunction "RP23(1)/CN17/PMA0/RC7_3") (pintype "passive"))
    )
    (net (code "100") (name "/RA0") (class "Default")
      (node (ref "U1") (pin "17") (pinfunction "TMS/SEG48/CTED0/CN33/RA0_17") (pintype "passive"))
    )
    (net (code "101") (name "/RA1") (class "Default")
      (node (ref "U1") (pin "38") (pinfunction "TCK/AN26/SEG31/CN34/RA1_38") (pintype "passive"))
    )
    (net (code "102") (name "/RA2") (class "Default")
      (node (ref "U1") (pin "58") (pinfunction "SEG55/SCL2/CN35/RA2_58") (pintype "passive"))
    )
    (net (code "103") (name "/RA3") (class "Default")
      (node (ref "U1") (pin "59") (pinfunction "SEG56/SDA2/PMA20/CN36/RA3_59") (pintype "passive"))
    )
    (net (code "104") (name "/RA4") (class "Default")
      (node (ref "U1") (pin "60") (pinfunction "TDI/AN36/SEG29/PMA21/CN37/RA4_60") (pintype "passive"))
    )
    (net (code "105") (name "/RA5") (class "Default")
      (node (ref "U1") (pin "61") (pinfunction "TDO/AN37/SEG28/CN38/RA5_61") (pintype "passive"))
    )
    (net (code "106") (name "/RA6") (class "Default")
      (node (ref "U1") (pin "91") (pinfunction "AN23/SEG57/CN39/RA6_91") (pintype "passive"))
    )
    (net (code "107") (name "/RA7") (class "Default")
      (node (ref "U1") (pin "92") (pinfunction "AN22/SEG58/PMA17/CN40/RA7_92") (pintype "passive"))
    )
    (net (code "108") (name "/RA14") (class "Default")
      (node (ref "U1") (pin "66") (pinfunction "AN38/SEG42/RPI36/SCL1/OCTRIG2/PMA22/CN43/RA14_66") (pintype "passive"))
    )
    (net (code "109") (name "/RA15") (class "Default")
      (node (ref "U1") (pin "67") (pinfunction "AN39/SEG43/RPI35/SDA1/PMBE1/CN44/RA15_67") (pintype "passive"))
    )
    (net (code "110") (name "/RB0") (class "Default")
      (node (ref "U1") (pin "25") (pinfunction "PGED1/CVREF+/AVREF+/DVREF+/BGBUF1/AN0/SEG7/RP0/CN2/RB0_25") (pintype "passive"))
    )
    (net (code "111") (name "/RB1") (class "Default")
      (node (ref "U1") (pin "24") (pinfunction "PGEC1/CVREF-/AVREF-/AN1/OA2P1/SEG6/RP1/CTED12/CN3/RB1_24") (pintype "passive"))
    )
    (net (code "112") (name "/RB2") (class "Default")
      (node (ref "U1") (pin "23") (pinfunction "AN2/OA2N2/CTCMP/C2INB/SEG5/RP13/T4CK/VMIO/CTED13/CN4/RB2_23") (pintype "passive"))
    )
    (net (code "113") (name "/RB5") (class "Default")
      (node (ref "U1") (pin "21") (pinfunction "PGED3/AN4/OA1N0/C1INB/SEG3/RP28/USBOEN/CN6/RB4_21") (pintype "passive"))
    )
    (net (code "114") (name "/RC1") (class "Default")
      (node (ref "U1") (pin "6") (pinfunction "AN8/OA1N1/SEG32/RPI38/CN45/RC1_6") (pintype "passive"))
    )
    (net (code "115") (name "/RC2") (class "Default")
      (node (ref "U1") (pin "7") (pinfunction "SEG51/RPI39/CN46/RC2_7") (pintype "passive"))
    )
    (net (code "116") (name "/RC3") (class "Default")
      (node (ref "U1") (pin "8") (pinfunction "AN9/SEG33/RPI40/CN47/RC3_8") (pintype "passive"))
    )
    (net (code "117") (name "/RC4") (class "Default")
      (node (ref "U1") (pin "9") (pinfunction "AN16/SEG52/RPI41/PMCS2/CN48/RC4_9") (pintype "passive"))
    )
    (net (code "118") (name "/RC13") (class "Default")
      (node (ref "U1") (pin "73") (pinfunction "SOSCI/RC13_73") (pintype "passive"))
    )
    (net (code "119") (name "/RC14") (class "Default")
      (node (ref "U1") (pin "74") (pinfunction "PWRLCLK/SOSCO/SCLKI/RPI37/RC14_74") (pintype "passive"))
    )
    (net (code "120") (name "/RD0") (class "Default")
      (node (ref "U1") (pin "72") (pinfunction "AN43/OA2N0/SEG17/RP11/VCMPST3/DMH/INT0/CN49/RD0_72") (pintype "passive"))
    )
    (net (code "121") (name "/RD1") (class "Default")
      (node (ref "U1") (pin "76") (pinfunction "AN35/SEG20/RP24/CN50/RD1(4)_76") (pintype "passive"))
    )
    (net (code "122") (name "/RD9") (class "Default")
      (node (ref "U1") (pin "69") (pinfunction "AN24/SEG14/RP4/DPLN/PMACK2/CN54/RD9_69") (pintype "passive"))
    )
    (net (code "123") (name "/RD14") (class "Default")
      (node (ref "U1") (pin "47") (pinfunction "AN28/SEG38/RPI43/CN20/RD14_47") (pintype "passive"))
    )
    (net (code "124") (name "/RD15") (class "Default")
      (node (ref "U1") (pin "48") (pinfunction "AN29/SEG39/RP5/CN21/RD15_48") (pintype "passive"))
    )
    (net (code "125") (name "/RE8") (class "Default")
      (node (ref "U1") (pin "18") (pinfunction "SEG34/RPI33/PMCS1/CN66/RE8_18") (pintype "passive"))
    )
    (net (code "126") (name "/RE9") (class "Default")
      (node (ref "U1") (pin "19") (pinfunction "AN21/SEG35/RPI34/PMA19/CN67/RE9_19") (pintype "passive"))
    )
    (net (code "127") (name "/RF2") (class "Default")
      (node (ref "U1") (pin "52") (pinfunction "AN31/SEG40/RP30/CN70/RF2_52") (pintype "passive"))
    )
    (net (code "128") (name "/RF8") (class "Default")
      (node (ref "U1") (pin "53") (pinfunction "AN32/SEG41/RP15/CN74/RF8_53") (pintype "passive"))
    )
    (net (code "129") (name "/RF12") (class "Default")
      (node (ref "U1") (pin "40") (pinfunction "SEG54/RPI32/CTED7/PMA18/CN75/RF12_40") (pintype "passive"))
    )
    (net (code "130") (name "/RF13") (class "Default")
      (node (ref "U1") (pin "39") (pinfunction "AN27/SEG53/RP31/CN76/RF13_39") (pintype "passive"))
    )
    (net (code "131") (name "/RG12") (class "Default")
      (node (ref "U1") (pin "96") (pinfunction "SEG60/CN79/RG12_96") (pintype "passive"))
    )
    (net (code "132") (name "/RG13") (class "Default")
      (node (ref "U1") (pin "97") (pinfunction "SEG61/CTED10/CN80/RG13_97") (pintype "passive"))
    )
    (net (code "133") (name "/RG14") (class "Default")
      (node (ref "U1") (pin "95") (pinfunction "SEG59/CTED11/PMA16/CN81/RG14_95") (pintype "passive"))
    )
    (net (code "134") (name "/RG15") (class "Default")
      (node (ref "U1") (pin "1") (pinfunction "AN33/SEG50/CTED3/CN82/RG15_1") (pintype "passive"))
    )
    (net (code "135") (name "/VBAT") (class "Default")
      (node (ref "U1") (pin "86") (pinfunction "VBAT_86") (pintype "passive"))
    )
    (net (code "136") (name "/VCAPPIC24") (class "Default")
      (node (ref "C3") (pin "2") (pinfunction "2_2") (pintype "passive"))
      (node (ref "U1") (pin "85") (pinfunction "VCAP_85") (pintype "passive"))
    )
    (net (code "137") (name "/VCAPPIC33") (class "Default")
      (node (ref "C4") (pin "2") (pinfunction "2_2") (pintype "passive"))
      (node (ref "U2") (pin "7") (pinfunction "VCAP_7") (pintype "passive"))
    )
    (net (code "138") (name "/VCC") (class "Default")
      (node (ref "R34") (pin "1") (pinfunction "1_1") (pintype "passive"))
      (node (ref "R36") (pin "1") (pinfunction "1_1") (pintype "passive"))
      (node (ref "R42") (pin "1") (pinfunction "1_1") (pintype "passive"))
      (node (ref "U5") (pin "8") (pinfunction "VCC_8") (pintype "passive"))
      (node (ref "U6") (pin "4") (pinfunction "VCC_4") (pintype "passive"))
    )
    (net (code "139") (name "/VCC-") (class "Default")
      (node (ref "R35") (pin "1") (pinfunction "1_1") (pintype "passive"))
      (node (ref "R41") (pin "1") (pinfunction "1_1") (pintype "passive"))
      (node (ref "R43") (pin "1") (pinfunction "1_1") (pintype "passive"))
      (node (ref "R44") (pin "1") (pinfunction "1_1") (pintype "passive"))
      (node (ref "R45") (pin "1") (pinfunction "1_1") (pintype "passive"))
      (node (ref "R46") (pin "1") (pinfunction "1_1") (pintype "passive"))
      (node (ref "U5") (pin "4") (pinfunction "GND_4") (pintype "passive"))
      (node (ref "U6") (pin "11") (pinfunction "GND_11") (pintype "passive"))
    )
    (net (code "140") (name "/VCC_HALF") (class "Default")
      (node (ref "R22") (pin "2") (pinfunction "2_2") (pintype "passive"))
      (node (ref "R23") (pin "2") (pinfunction "2_2") (pintype "passive"))
      (node (ref "R32") (pin "2") (pinfunction "2_2") (pintype "passive"))
      (node (ref "R33") (pin "2") (pinfunction "2_2") (pintype "passive"))
    )
    (net (code "141") (name "/VDD") (class "Default")
      (node (ref "C7") (pin "2") (pinfunction "2_2") (pintype "passive"))
      (node (ref "J3") (pin "2") (pinfunction "2_2") (pintype "passive"))
      (node (ref "J4") (pin "2") (pinfunction "2_2") (pintype "passive"))
      (node (ref "R1") (pin "2") (pinfunction "2_2") (pintype "passive"))
      (node (ref "R2") (pin "2") (pinfunction "2_2") (pintype "passive"))
      (node (ref "R36") (pin "2") (pinfunction "2_2") (pintype "passive"))
      (node (ref "U1") (pin "16") (pinfunction "VDD_16") (pintype "passive"))
      (node (ref "U1") (pin "2") (pinfunction "VDD_2") (pintype "passive"))
      (node (ref "U1") (pin "46") (pinfunction "VDD_46") (pintype "passive"))
      (node (ref "U1") (pin "55") (pinfunction "VUSB3V3_55") (pintype "passive"))
      (node (ref "U1") (pin "62") (pinfunction "VDD_62") (pintype "passive"))
      (node (ref "U2") (pin "28") (pinfunction "VDD_28") (pintype "passive"))
      (node (ref "U2") (pin "40") (pinfunction "VDD_40") (pintype "passive"))
      (node (ref "U3") (pin "5") (pinfunction "Vout_5") (pintype "passive"))
    )
    (net (code "142") (name "GND") (class "Default")
      (node (ref "C1") (pin "1") (pinfunction "1_1") (pintype "passive"))
      (node (ref "C2") (pin "1") (pinfunction "1_1") (pintype "passive"))
      (node (ref "C3") (pin "1") (pinfunction "1_1") (pintype "passive"))
      (node (ref "C4") (pin "1") (pinfunction "1_1") (pintype "passive"))
      (node (ref "C5") (pin "1") (pinfunction "1_1") (pintype "passive"))
      (node (ref "C6") (pin "1") (pinfunction "1_1") (pintype "passive"))
      (node (ref "C7") (pin "1") (pinfunction "1_1") (pintype "passive"))
      (node (ref "D1") (pin "2") (pinfunction "AAAA_2") (pintype "passive"))
      (node (ref "D1") (pin "5") (pinfunction "C4_5") (pintype "passive"))
      (node (ref "D2") (pin "1") (pinfunction "A_1") (pintype "passive"))
      (node (ref "D3") (pin "1") (pinfunction "A_1") (pintype "passive"))
      (node (ref "J14") (pin "2") (pinfunction "2_2") (pintype "passive"))
      (node (ref "J3") (pin "3") (pinfunction "3_3") (pintype "passive"))
      (node (ref "J4") (pin "3") (pinfunction "3_3") (pintype "passive"))
      (node (ref "J5") (pin "5") (pinfunction "5_5") (pintype "passive"))
      (node (ref "J5") (pin "6") (pinfunction "6_6") (pintype "passive"))
      (node (ref "J5") (pin "7") (pinfunction "7_7") (pintype "passive"))
      (node (ref "J5") (pin "8") (pinfunction "8_8") (pintype "passive"))
      (node (ref "J5") (pin "9") (pinfunction "9_9") (pintype "passive"))
      (node (ref "R41") (pin "2") (pinfunction "2_2") (pintype "passive"))
      (node (ref "R5") (pin "1") (pinfunction "1_1") (pintype "passive"))
      (node (ref "U1") (pin "15") (pinfunction "VSS_15") (pintype "passive"))
      (node (ref "U1") (pin "45") (pinfunction "VSS_45") (pintype "passive"))
      (node (ref "U1") (pin "65") (pinfunction "VSS_65") (pintype "passive"))
      (node (ref "U1") (pin "75") (pinfunction "VSS_75") (pintype "passive"))
      (node (ref "U2") (pin "29") (pinfunction "VSS_29") (pintype "passive"))
      (node (ref "U2") (pin "39") (pinfunction "VSS_39") (pintype "passive"))
      (node (ref "U2") (pin "6") (pinfunction "VSS_6") (pintype "passive"))
      (node (ref "U3") (pin "2") (pinfunction "GND_2") (pintype "passive"))
    )
    (net (code "143") (name "unconnected-(J6-Pad1)") (class "Default")
      (node (ref "J6") (pin "1") (pinfunction "1_1") (pintype "passive"))
    )
    (net (code "144") (name "unconnected-(J7-Pad1)") (class "Default")
      (node (ref "J7") (pin "1") (pinfunction "1_1") (pintype "passive"))
    )
    (net (code "145") (name "unconnected-(J8-Pad1)") (class "Default")
      (node (ref "J8") (pin "1") (pinfunction "1_1") (pintype "passive"))
    )
    (net (code "146") (name "unconnected-(J9-Pad1)") (class "Default")
      (node (ref "J9") (pin "1") (pinfunction "1_1") (pintype "passive"))
    )
    (net (code "147") (name "unconnected-(U3-NC-Pad4)") (class "Default")
      (node (ref "U3") (pin "4") (pinfunction "NC_4") (pintype "passive"))
    )
    (net (code "148") (name "unconnected-(Y1-NC-Pad2)") (class "Default")
      (node (ref "Y1") (pin "2") (pinfunction "NC_2") (pintype "passive"))
    )
    (net (code "149") (name "unconnected-(Y1-NC-Pad4)") (class "Default")
      (node (ref "Y1") (pin "4") (pinfunction "NC_4") (pintype "passive"))
    )
  )
)
